# CarrierConnector.net
KiCad netlist of a schematic drawn in Altium Designer
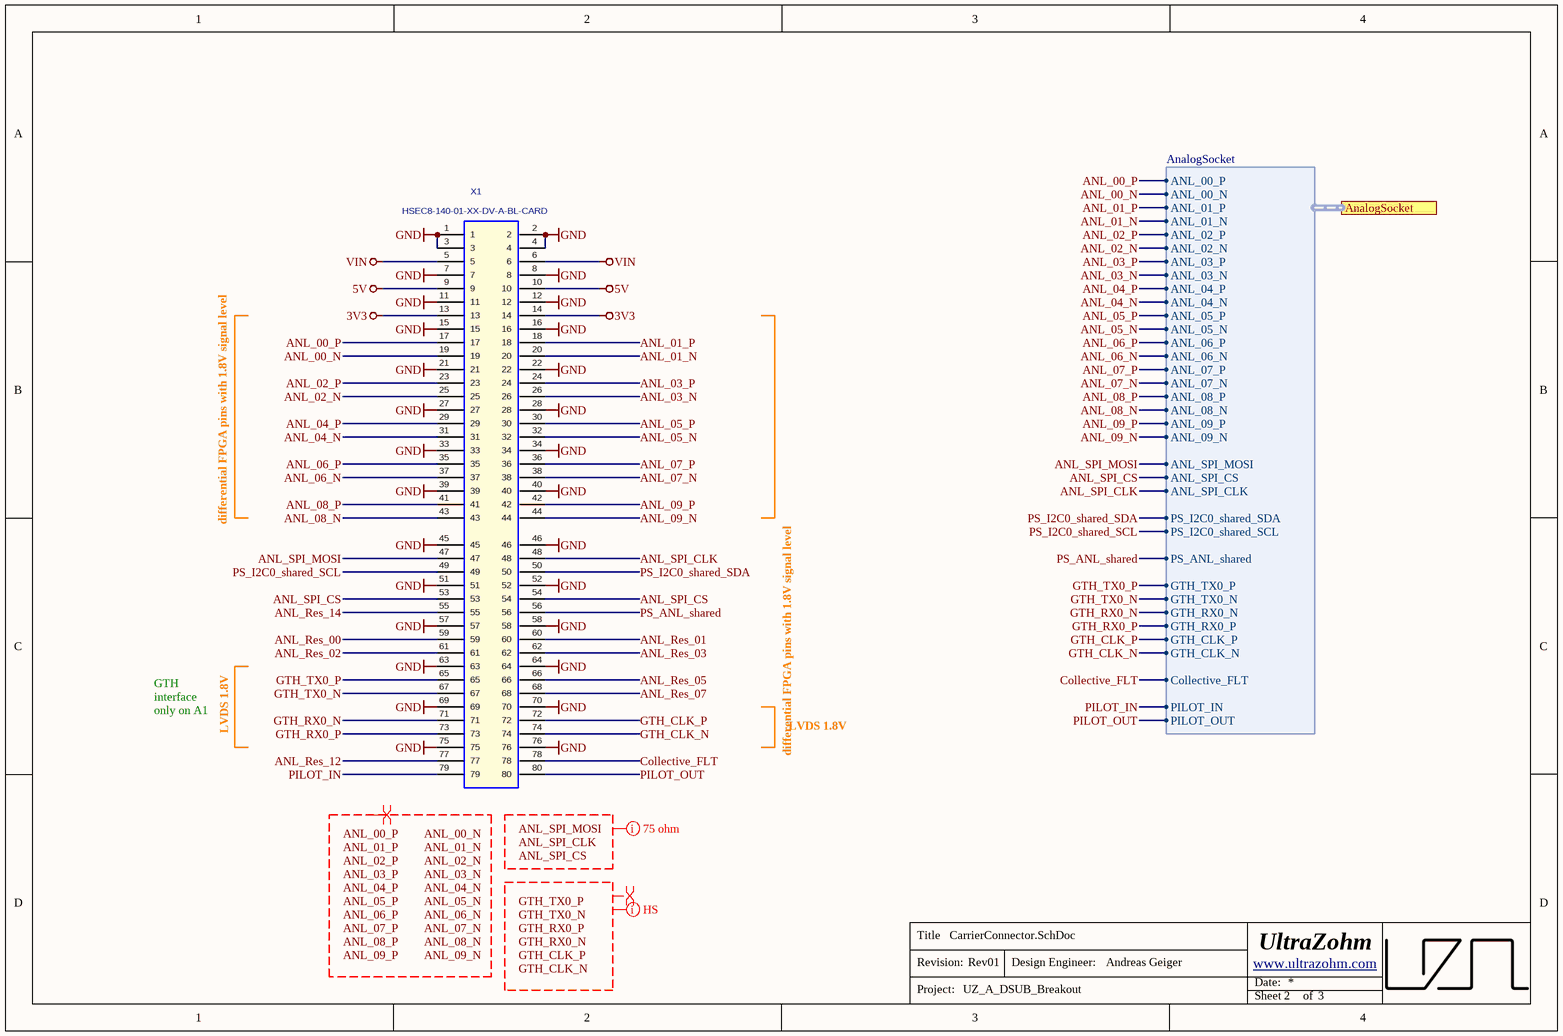
[diagram p0: CarrierConnector.SchDoc]

(export (version "E")
  (design (tool "Eeschema 10.0.6"))
  (components
    (comp (ref "X1")
      (value "HSEC8-140-01-XX-DV-A-BL-CARD")
      (footprint "HSEC8-140-01-XX-DV-A-BL-CARD")
      (description "Mating Card Layout for HSEC8-140-01-XX-DV-A-BL-CARD")
      (fields
        (field (name "MANUFACTURER") "SAMTEC")
        (field (name "CREATED") "2018_04_23_AGeiger")
        (field (name "CREATED FROM") "MHlatky")
      )
      (libsource (lib "user") (part "HSEC8-140-01-XX-DV-A-BL-CARD"))
    )
  )
  (nets
    (net (code "2") (name "/ANL_00_N") (class "Default")
      (node (ref "X1") (pin "19") (pinfunction "19_19") (pintype "passive"))
    )
    (net (code "3") (name "/ANL_00_P") (class "Default")
      (node (ref "X1") (pin "17") (pinfunction "17_17") (pintype "passive"))
    )
    (net (code "4") (name "/ANL_01_N") (class "Default")
      (node (ref "X1") (pin "20") (pinfunction "20_20") (pintype "passive"))
    )
    (net (code "5") (name "/ANL_01_P") (class "Default")
      (node (ref "X1") (pin "18") (pinfunction "18_18") (pintype "passive"))
    )
    (net (code "6") (name "/ANL_02_N") (class "Default")
      (node (ref "X1") (pin "25") (pinfunction "25_25") (pintype "passive"))
    )
    (net (code "7") (name "/ANL_02_P") (class "Default")
      (node (ref "X1") (pin "23") (pinfunction "23_23") (pintype "passive"))
    )
    (net (code "8") (name "/ANL_03_N") (class "Default")
      (node (ref "X1") (pin "26") (pinfunction "26_26") (pintype "passive"))
    )
    (net (code "9") (name "/ANL_03_P") (class "Default")
      (node (ref "X1") (pin "24") (pinfunction "24_24") (pintype "passive"))
    )
    (net (code "10") (name "/ANL_04_N") (class "Default")
      (node (ref "X1") (pin "31") (pinfunction "31_31") (pintype "passive"))
    )
    (net (code "11") (name "/ANL_04_P") (class "Default")
      (node (ref "X1") (pin "29") (pinfunction "29_29") (pintype "passive"))
    )
    (net (code "12") (name "/ANL_05_N") (class "Default")
      (node (ref "X1") (pin "32") (pinfunction "32_32") (pintype "passive"))
    )
    (net (code "13") (name "/ANL_05_P") (class "Default")
      (node (ref "X1") (pin "30") (pinfunction "30_30") (pintype "passive"))
    )
    (net (code "14") (name "/ANL_06_N") (class "Default")
      (node (ref "X1") (pin "37") (pinfunction "37_37") (pintype "passive"))
    )
    (net (code "15") (name "/ANL_06_P") (class "Default")
      (node (ref "X1") (pin "35") (pinfunction "35_35") (pintype "passive"))
    )
    (net (code "16") (name "/ANL_07_N") (class "Default")
      (node (ref "X1") (pin "38") (pinfunction "38_38") (pintype "passive"))
    )
    (net (code "17") (name "/ANL_07_P") (class "Default")
      (node (ref "X1") (pin "36") (pinfunction "36_36") (pintype "passive"))
    )
    (net (code "18") (name "/ANL_08_N") (class "Default")
      (node (ref "X1") (pin "43") (pinfunction "43_43") (pintype "passive"))
    )
    (net (code "19") (name "/ANL_08_P") (class "Default")
      (node (ref "X1") (pin "41") (pinfunction "41_41") (pintype "passive"))
    )
    (net (code "20") (name "/ANL_09_N") (class "Default")
      (node (ref "X1") (pin "44") (pinfunction "44_44") (pintype "passive"))
    )
    (net (code "21") (name "/ANL_09_P") (class "Default")
      (node (ref "X1") (pin "42") (pinfunction "42_42") (pintype "passive"))
    )
    (net (code "22") (name "/ANL_Res_00") (class "Default")
      (node (ref "X1") (pin "59") (pinfunction "59_59") (pintype "passive"))
    )
    (net (code "23") (name "/ANL_Res_01") (class "Default")
      (node (ref "X1") (pin "60") (pinfunction "60_60") (pintype "passive"))
    )
    (net (code "24") (name "/ANL_Res_02") (class "Default")
      (node (ref "X1") (pin "61") (pinfunction "61_61") (pintype "passive"))
    )
    (net (code "25") (name "/ANL_Res_03") (class "Default")
      (node (ref "X1") (pin "62") (pinfunction "62_62") (pintype "passive"))
    )
    (net (code "26") (name "/ANL_Res_05") (class "Default")
      (node (ref "X1") (pin "66") (pinfunction "66_66") (pintype "passive"))
    )
    (net (code "27") (name "/ANL_Res_07") (class "Default")
      (node (ref "X1") (pin "68") (pinfunction "68_68") (pintype "passive"))
    )
    (net (code "28") (name "/ANL_Res_12") (class "Default")
      (node (ref "X1") (pin "77") (pinfunction "77_77") (pintype "passive"))
    )
    (net (code "29") (name "/ANL_Res_14") (class "Default")
      (node (ref "X1") (pin "55") (pinfunction "55_55") (pintype "passive"))
    )
    (net (code "30") (name "/ANL_SPI_CLK") (class "Default")
      (node (ref "X1") (pin "48") (pinfunction "48_48") (pintype "passive"))
    )
    (net (code "31") (name "/ANL_SPI_CS") (class "Default")
      (node (ref "X1") (pin "53") (pinfunction "53_53") (pintype "passive"))
      (node (ref "X1") (pin "54") (pinfunction "54_54") (pintype "passive"))
    )
    (net (code "32") (name "/ANL_SPI_MOSI") (class "Default")
      (node (ref "X1") (pin "47") (pinfunction "47_47") (pintype "passive"))
    )
    (net (code "33") (name "/Collective_FLT") (class "Default")
      (node (ref "X1") (pin "78") (pinfunction "78_78") (pintype "passive"))
    )
    (net (code "34") (name "/GTH_CLK_N") (class "Default")
      (node (ref "X1") (pin "74") (pinfunction "74_74") (pintype "passive"))
    )
    (net (code "35") (name "/GTH_CLK_P") (class "Default")
      (node (ref "X1") (pin "72") (pinfunction "72_72") (pintype "passive"))
    )
    (net (code "36") (name "/GTH_RX0_N") (class "Default")
      (node (ref "X1") (pin "71") (pinfunction "71_71") (pintype "passive"))
    )
    (net (code "37") (name "/GTH_RX0_P") (class "Default")
      (node (ref "X1") (pin "73") (pinfunction "73_73") (pintype "passive"))
    )
    (net (code "38") (name "/GTH_TX0_N") (class "Default")
      (node (ref "X1") (pin "67") (pinfunction "67_67") (pintype "passive"))
    )
    (net (code "39") (name "/GTH_TX0_P") (class "Default")
      (node (ref "X1") (pin "65") (pinfunction "65_65") (pintype "passive"))
    )
    (net (code "40") (name "/PILOT_IN") (class "Default")
      (node (ref "X1") (pin "79") (pinfunction "79_79") (pintype "passive"))
    )
    (net (code "41") (name "/PILOT_OUT") (class "Default")
      (node (ref "X1") (pin "80") (pinfunction "80_80") (pintype "passive"))
    )
    (net (code "42") (name "/PS_ANL_shared") (class "Default")
      (node (ref "X1") (pin "56") (pinfunction "56_56") (pintype "passive"))
    )
    (net (code "43") (name "/PS_I2C0_shared_SCL") (class "Default")
      (node (ref "X1") (pin "49") (pinfunction "49_49") (pintype "passive"))
    )
    (net (code "44") (name "/PS_I2C0_shared_SDA") (class "Default")
      (node (ref "X1") (pin "50") (pinfunction "50_50") (pintype "passive"))
    )
    (net (code "46") (name "3V3") (class "Default")
      (node (ref "X1") (pin "13") (pinfunction "13_13") (pintype "passive"))
      (node (ref "X1") (pin "14") (pinfunction "14_14") (pintype "passive"))
    )
    (net (code "47") (name "5V") (class "Default")
      (node (ref "X1") (pin "10") (pinfunction "10_10") (pintype "passive"))
      (node (ref "X1") (pin "9") (pinfunction "9_9") (pintype "passive"))
    )
    (net (code "48") (name "GND") (class "Default")
      (node (ref "X1") (pin "1") (pinfunction "1_1") (pintype "passive"))
      (node (ref "X1") (pin "11") (pinfunction "11_11") (pintype "passive"))
      (node (ref "X1") (pin "12") (pinfunction "12_12") (pintype "passive"))
      (node (ref "X1") (pin "15") (pinfunction "15_15") (pintype "passive"))
      (node (ref "X1") (pin "16") (pinfunction "16_16") (pintype "passive"))
      (node (ref "X1") (pin "2") (pinfunction "2_2") (pintype "passive"))
      (node (ref "X1") (pin "21") (pinfunction "21_21") (pintype "passive"))
      (node (ref "X1") (pin "22") (pinfunction "22_22") (pintype "passive"))
      (node (ref "X1") (pin "27") (pinfunction "27_27") (pintype "passive"))
      (node (ref "X1") (pin "28") (pinfunction "28_28") (pintype "passive"))
      (node (ref "X1") (pin "3") (pinfunction "3_3") (pintype "passive"))
      (node (ref "X1") (pin "33") (pinfunction "33_33") (pintype "passive"))
      (node (ref "X1") (pin "34") (pinfunction "34_34") (pintype "passive"))
      (node (ref "X1") (pin "39") (pinfunction "39_39") (pintype "passive"))
      (node (ref "X1") (pin "4") (pinfunction "4_4") (pintype "passive"))
      (node (ref "X1") (pin "40") (pinfunction "40_40") (pintype "passive"))
      (node (ref "X1") (pin "45") (pinfunction "45_45") (pintype "passive"))
      (node (ref "X1") (pin "46") (pinfunction "46_46") (pintype "passive"))
      (node (ref "X1") (pin "51") (pinfunction "51_51") (pintype "passive"))
      (node (ref "X1") (pin "52") (pinfunction "52_52") (pintype "passive"))
      (node (ref "X1") (pin "57") (pinfunction "57_57") (pintype "passive"))
      (node (ref "X1") (pin "58") (pinfunction "58_58") (pintype "passive"))
      (node (ref "X1") (pin "63") (pinfunction "63_63") (pintype "passive"))
      (node (ref "X1") (pin "64") (pinfunction "64_64") (pintype "passive"))
      (node (ref "X1") (pin "69") (pinfunction "69_69") (pintype "passive"))
      (node (ref "X1") (pin "7") (pinfunction "7_7") (pintype "passive"))
      (node (ref "X1") (pin "70") (pinfunction "70_70") (pintype "passive"))
      (node (ref "X1") (pin "75") (pinfunction "75_75") (pintype "passive"))
      (node (ref "X1") (pin "76") (pinfunction "76_76") (pintype "passive"))
      (node (ref "X1") (pin "8") (pinfunction "8_8") (pintype "passive"))
    )
    (net (code "49") (name "VIN") (class "Default")
      (node (ref "X1") (pin "5") (pinfunction "5_5") (pintype "passive"))
      (node (ref "X1") (pin "6") (pinfunction "6_6") (pintype "passive"))
    )
  )
)
